# 2012_BALISE_CONNECTIQUE_FILLE.net
KiCad netlist of a schematic drawn in Altium Designer
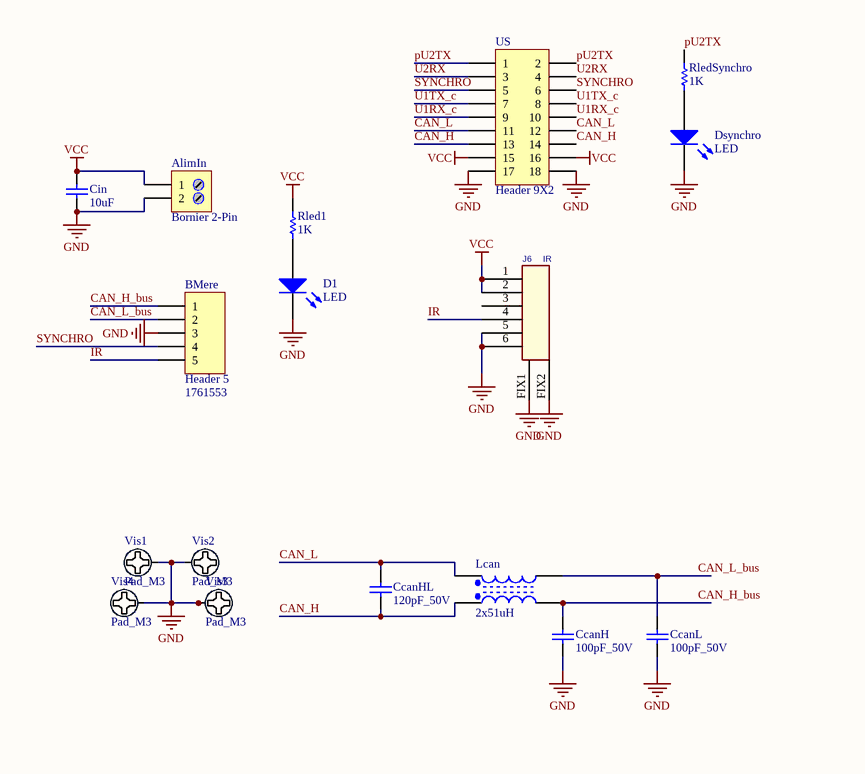
[diagram p0: 2012_BALISE_CONNECTIQUE_FILLE.SchDoc, left]
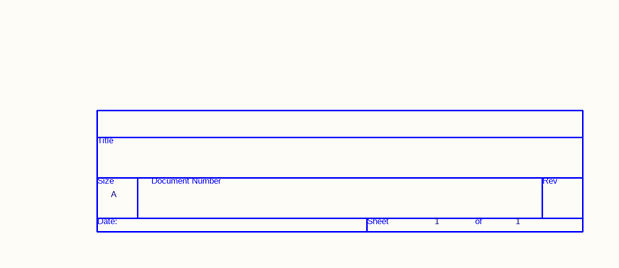
[diagram p1: 2012_BALISE_CONNECTIQUE_FILLE.SchDoc, right]

(export (version "E")
  (design (tool "Eeschema 10.0.6"))
  (components
    (comp (ref "*")
      (value "TitleBlock0")
      (fields (field (name "PAGE COUNT") "1") (field (name "PAGE NUMBER") "1") (field (name "PAGE SIZE") "A"))
      (libsource (lib "*") (part "TitleBlock0"))
    )
    (comp (ref "AlimIn")
      (value "Bornier 2-Pin")
      (footprint "Bornier_2_pas 5.08mm")
      (fields (field (name "PUBLISHER") "Altium Limited"))
      (libsource (lib "DG_Connecteur") (part "Bornier 2-Pin"))
    )
    (comp (ref "BMere")
      (value "Header 5")
      (footprint "HDR1X5")
      (description "Header, 5-Pin")
      (fields (field (name "FAR") "1761553") (field (name "PUBLISHER") "Altium Limited"))
      (libsource (lib "DG_Connecteur") (part "Header 5"))
    )
    (comp (ref "CcanH")
      (value "100pF_50V")
      (footprint "C0603_N")
      (description "Capacitor")
      (fields (field (name "PUBLISHER") "Altium Limited"))
      (libsource (lib "DG_Condensateur") (part "Capacitor"))
    )
    (comp (ref "CcanHL")
      (value "120pF_50V")
      (footprint "C0603_N")
      (description "Capacitor")
      (fields (field (name "PUBLISHER") "Altium Limited"))
      (libsource (lib "DG_Condensateur") (part "Capacitor"))
    )
    (comp (ref "CcanL")
      (value "100pF_50V")
      (footprint "C0603_N")
      (description "Capacitor")
      (fields (field (name "PUBLISHER") "Altium Limited"))
      (libsource (lib "DG_Condensateur") (part "Capacitor"))
    )
    (comp (ref "Cin")
      (value "10uF")
      (footprint "C1206_N")
      (description "Capacitor")
      (fields (field (name "PUBLISHER") "Altium Limited"))
      (libsource (lib "DG_Condensateur") (part "Capacitor"))
    )
    (comp (ref "D1")
      (value "LED")
      (footprint "LED_0805")
      (description "Typical LED")
      (fields (field (name "PUBLISHER") "Altium Limited"))
      (libsource (lib "DG_LED") (part "LED"))
    )
    (comp (ref "Dsynchro")
      (value "LED")
      (footprint "LED_0805")
      (description "Typical LED")
      (fields (field (name "PUBLISHER") "Altium Limited"))
      (libsource (lib "DG_LED") (part "LED"))
    )
    (comp (ref "J6") (value "IR") (footprint "RJ11_6/6") (libsource (lib "*") (part "CONNECTEUR_RJ12")))
    (comp (ref "Lcan")
      (value "2x51uH")
      (footprint "Self de mode commun Wurth Elektronik WE-SL2")
      (description "WUERTH ELEKTRONIK - WE-SL2 744 227 - FILTRE DE LIGNE MODE COMMUN CMS 2X51uH")
      (fields (field (name "MANUFACTURER") "WURTH ELEKTRONIK"))
      (libsource (lib "DG_Inductance") (part "Self de mode commun WE-744220"))
    )
    (comp (ref "Rled1")
      (value "1K")
      (footprint "R1206_N")
      (description "Resistor")
      (fields (field (name "PUBLISHER") "Altium Limited"))
      (libsource (lib "DG_Resistance") (part "Resistor"))
    )
    (comp (ref "RledSynchro")
      (value "1K")
      (footprint "R1206_N")
      (description "Resistor")
      (fields (field (name "PUBLISHER") "Altium Limited"))
      (libsource (lib "DG_Resistance") (part "Resistor"))
    )
    (comp (ref "US")
      (value "Header 9X2")
      (footprint "HDR2X9")
      (description "Header, 9-Pin, Dual row")
      (fields (field (name "PUBLISHER") "Altium Limited"))
      (libsource (lib "DG_Connecteur") (part "Header 9X2"))
    )
    (comp (ref "Vis1")
      (value "Pad_M3")
      (footprint "M3x6mm")
      (description "Vis M3 X 6mm _TORX_Tête 6mm")
      (fields (field (name "PUBLISHER") "Damien Guitton"))
      (libsource (lib "DG_Mecanique") (part "Vis M3 X 6mm _TORX_Tête 6mm"))
    )
    (comp (ref "Vis2")
      (value "Pad_M3")
      (footprint "M3x6mm")
      (description "Vis M3 X 6mm _TORX_Tête 6mm")
      (fields (field (name "PUBLISHER") "Damien Guitton"))
      (libsource (lib "DG_Mecanique") (part "Vis M3 X 6mm _TORX_Tête 6mm"))
    )
    (comp (ref "Vis3")
      (value "Pad_M3")
      (footprint "M3x6mm")
      (description "Vis M3 X 6mm _TORX_Tête 6mm")
      (fields (field (name "PUBLISHER") "Damien Guitton"))
      (libsource (lib "DG_Mecanique") (part "Vis M3 X 6mm _TORX_Tête 6mm"))
    )
    (comp (ref "Vis4")
      (value "Pad_M3")
      (footprint "M3x6mm")
      (description "Vis M3 X 6mm _TORX_Tête 6mm")
      (fields (field (name "PUBLISHER") "Damien Guitton"))
      (libsource (lib "DG_Mecanique") (part "Vis M3 X 6mm _TORX_Tête 6mm"))
    )
  )
  (nets
    (net (code "1") (name "/CAN_H") (class "Default")
      (node (ref "CcanHL") (pin "1") (pinfunction "1_1") (pintype "passive"))
      (node (ref "Lcan") (pin "1") (pinfunction "1_1") (pintype "passive"))
      (node (ref "US") (pin "13") (pinfunction "13_13") (pintype "passive"))
      (node (ref "US") (pin "14") (pinfunction "14_14") (pintype "passive"))
    )
    (net (code "2") (name "/CAN_H_bus") (class "Default")
      (node (ref "BMere") (pin "1") (pinfunction "1_1") (pintype "passive"))
      (node (ref "CcanH") (pin "2") (pinfunction "2_2") (pintype "passive"))
      (node (ref "Lcan") (pin "4") (pinfunction "4_4") (pintype "passive"))
    )
    (net (code "3") (name "/CAN_L") (class "Default")
      (node (ref "CcanHL") (pin "2") (pinfunction "2_2") (pintype "passive"))
      (node (ref "Lcan") (pin "2") (pinfunction "2_2") (pintype "passive"))
      (node (ref "US") (pin "11") (pinfunction "11_11") (pintype "passive"))
      (node (ref "US") (pin "12") (pinfunction "12_12") (pintype "passive"))
    )
    (net (code "4") (name "/CAN_L_bus") (class "Default")
      (node (ref "BMere") (pin "2") (pinfunction "2_2") (pintype "passive"))
      (node (ref "CcanL") (pin "2") (pinfunction "2_2") (pintype "passive"))
      (node (ref "Lcan") (pin "3") (pinfunction "3_3") (pintype "passive"))
    )
    (net (code "5") (name "/IR") (class "Default")
      (node (ref "BMere") (pin "5") (pinfunction "5_5") (pintype "passive"))
      (node (ref "J6") (pin "4") (pinfunction "4_4") (pintype "passive"))
    )
    (net (code "6") (name "/SYNCHRO") (class "Default")
      (node (ref "BMere") (pin "4") (pinfunction "4_4") (pintype "passive"))
      (node (ref "US") (pin "5") (pinfunction "5_5") (pintype "passive"))
      (node (ref "US") (pin "6") (pinfunction "6_6") (pintype "passive"))
    )
    (net (code "7") (name "/U1RX_c") (class "Default")
      (node (ref "US") (pin "10") (pinfunction "10_10") (pintype "passive"))
      (node (ref "US") (pin "9") (pinfunction "9_9") (pintype "passive"))
    )
    (net (code "8") (name "/U1TX_c") (class "Default")
      (node (ref "US") (pin "7") (pinfunction "7_7") (pintype "passive"))
      (node (ref "US") (pin "8") (pinfunction "8_8") (pintype "passive"))
    )
    (net (code "9") (name "/U2RX") (class "Default")
      (node (ref "US") (pin "3") (pinfunction "3_3") (pintype "passive"))
      (node (ref "US") (pin "4") (pinfunction "4_4") (pintype "passive"))
    )
    (net (code "10") (name "/pU2TX") (class "Default")
      (node (ref "RledSynchro") (pin "2") (pinfunction "2_2") (pintype "passive"))
      (node (ref "US") (pin "1") (pinfunction "1_1") (pintype "passive"))
      (node (ref "US") (pin "2") (pinfunction "2_2") (pintype "passive"))
    )
    (net (code "11") (name "GND") (class "Default")
      (node (ref "AlimIn") (pin "2") (pinfunction "2_2") (pintype "passive"))
      (node (ref "BMere") (pin "3") (pinfunction "3_3") (pintype "passive"))
      (node (ref "CcanH") (pin "1") (pinfunction "1_1") (pintype "passive"))
      (node (ref "CcanL") (pin "1") (pinfunction "1_1") (pintype "passive"))
      (node (ref "Cin") (pin "1") (pinfunction "1_1") (pintype "passive"))
      (node (ref "D1") (pin "2") (pinfunction "2_2") (pintype "passive"))
      (node (ref "Dsynchro") (pin "2") (pinfunction "2_2") (pintype "passive"))
      (node (ref "J6") (pin "5") (pinfunction "5_5") (pintype "passive"))
      (node (ref "J6") (pin "6") (pinfunction "6_6") (pintype "passive"))
      (node (ref "J6") (pin "FIX1") (pinfunction "FIX1_FIX1") (pintype "passive"))
      (node (ref "J6") (pin "FIX2") (pinfunction "FIX2_FIX2") (pintype "passive"))
      (node (ref "US") (pin "17") (pinfunction "17_17") (pintype "passive"))
      (node (ref "US") (pin "18") (pinfunction "18_18") (pintype "passive"))
      (node (ref "Vis1") (pin "1") (pinfunction "1_1") (pintype "passive"))
      (node (ref "Vis2") (pin "1") (pinfunction "1_1") (pintype "passive"))
      (node (ref "Vis3") (pin "1") (pinfunction "1_1") (pintype "passive"))
      (node (ref "Vis4") (pin "1") (pinfunction "1_1") (pintype "passive"))
    )
    (net (code "12") (name "Net-(D1-Pad1)") (class "Default")
      (node (ref "D1") (pin "1") (pinfunction "1_1") (pintype "passive"))
      (node (ref "Rled1") (pin "1") (pinfunction "1_1") (pintype "passive"))
    )
    (net (code "13") (name "Net-(Dsynchro-Pad1)") (class "Default")
      (node (ref "Dsynchro") (pin "1") (pinfunction "1_1") (pintype "passive"))
      (node (ref "RledSynchro") (pin "1") (pinfunction "1_1") (pintype "passive"))
    )
    (net (code "14") (name "VCC") (class "Default")
      (node (ref "AlimIn") (pin "1") (pinfunction "1_1") (pintype "passive"))
      (node (ref "Cin") (pin "2") (pinfunction "2_2") (pintype "passive"))
      (node (ref "J6") (pin "1") (pinfunction "1_1") (pintype "passive"))
      (node (ref "J6") (pin "2") (pinfunction "2_2") (pintype "passive"))
      (node (ref "Rled1") (pin "2") (pinfunction "2_2") (pintype "passive"))
      (node (ref "US") (pin "15") (pinfunction "15_15") (pintype "passive"))
      (node (ref "US") (pin "16") (pinfunction "16_16") (pintype "passive"))
    )
    (net (code "15") (name "unconnected-(J6-Pad3)") (class "Default")
      (node (ref "J6") (pin "3") (pinfunction "3_3") (pintype "passive"))
    )
  )
)
